# 10-Cooling_Sensors.net
KiCad netlist of a schematic drawn in Altium Designer
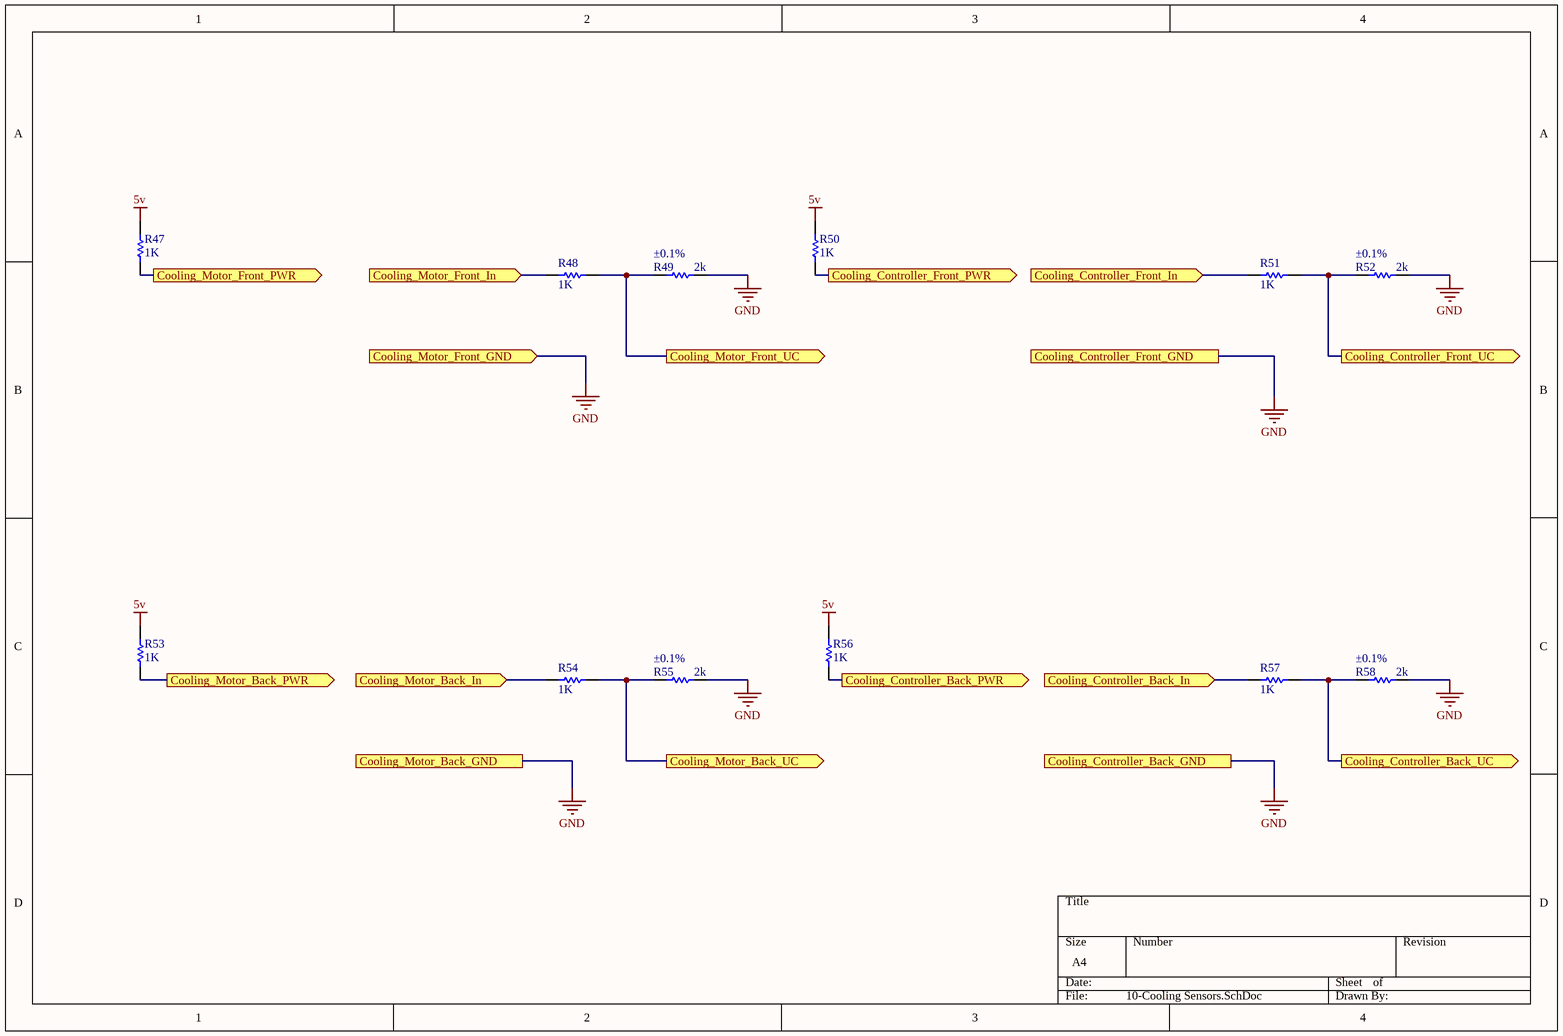
[diagram p0: 10-Cooling Sensors.SchDoc]

(export (version "E")
  (design (tool "Eeschema 10.0.6"))
  (components
    (comp (ref "R47")
      (value "1K")
      (footprint "1608[0603]")
      (description "Resistor")
      (fields (field (name "Comment") "Res1") (field (name "PUBLISHER") "Altium Limited"))
      (libsource (lib "Miscellaneous Devices") (part "Res1"))
    )
    (comp (ref "R48")
      (value "1K")
      (footprint "1608[0603]")
      (description "Resistor")
      (fields (field (name "Comment") "Res1") (field (name "PUBLISHER") "Altium Limited"))
      (libsource (lib "Miscellaneous Devices") (part "Res1"))
    )
    (comp (ref "R49")
      (value "2k")
      (footprint "1608[0603]")
      (description "Resistor")
      (fields
        (field (name "MANUFACTURER") "Yageo")
        (field (name "MANUFACTURER PART NUMBER") "AT0603BRD072KL")
        (field (name "TOLERANCE") "±0.1%")
      )
      (libsource (lib "Miscellaneous Devices") (part "Res1"))
    )
    (comp (ref "R50")
      (value "1K")
      (footprint "1608[0603]")
      (description "Resistor")
      (fields (field (name "Comment") "Res1") (field (name "PUBLISHER") "Altium Limited"))
      (libsource (lib "Miscellaneous Devices") (part "Res1"))
    )
    (comp (ref "R51")
      (value "1K")
      (footprint "1608[0603]")
      (description "Resistor")
      (fields (field (name "Comment") "Res1") (field (name "PUBLISHER") "Altium Limited"))
      (libsource (lib "Miscellaneous Devices") (part "Res1"))
    )
    (comp (ref "R52")
      (value "2k")
      (footprint "1608[0603]")
      (description "Resistor")
      (fields
        (field (name "MANUFACTURER") "Yageo")
        (field (name "MANUFACTURER PART NUMBER") "AT0603BRD072KL")
        (field (name "TOLERANCE") "±0.1%")
      )
      (libsource (lib "Miscellaneous Devices") (part "Res1"))
    )
    (comp (ref "R53")
      (value "1K")
      (footprint "1608[0603]")
      (description "Resistor")
      (fields (field (name "Comment") "Res1") (field (name "PUBLISHER") "Altium Limited"))
      (libsource (lib "Miscellaneous Devices") (part "Res1"))
    )
    (comp (ref "R54")
      (value "1K")
      (footprint "1608[0603]")
      (description "Resistor")
      (fields (field (name "Comment") "Res1") (field (name "PUBLISHER") "Altium Limited"))
      (libsource (lib "Miscellaneous Devices") (part "Res1"))
    )
    (comp (ref "R55")
      (value "2k")
      (footprint "1608[0603]")
      (description "Resistor")
      (fields
        (field (name "MANUFACTURER") "Yageo")
        (field (name "MANUFACTURER PART NUMBER") "AT0603BRD072KL")
        (field (name "TOLERANCE") "±0.1%")
      )
      (libsource (lib "Miscellaneous Devices") (part "Res1"))
    )
    (comp (ref "R56")
      (value "1K")
      (footprint "1608[0603]")
      (description "Resistor")
      (fields (field (name "Comment") "Res1") (field (name "PUBLISHER") "Altium Limited"))
      (libsource (lib "Miscellaneous Devices") (part "Res1"))
    )
    (comp (ref "R57")
      (value "1K")
      (footprint "1608[0603]")
      (description "Resistor")
      (fields (field (name "Comment") "Res1") (field (name "PUBLISHER") "Altium Limited"))
      (libsource (lib "Miscellaneous Devices") (part "Res1"))
    )
    (comp (ref "R58")
      (value "2k")
      (footprint "1608[0603]")
      (description "Resistor")
      (fields
        (field (name "MANUFACTURER") "Yageo")
        (field (name "MANUFACTURER PART NUMBER") "AT0603BRD072KL")
        (field (name "TOLERANCE") "±0.1%")
      )
      (libsource (lib "Miscellaneous Devices") (part "Res1"))
    )
  )
  (nets
    (net (code "1") (name "/Cooling_Controller_Back_In") (class "Default")
      (node (ref "R57") (pin "2") (pinfunction "2_2") (pintype "passive"))
    )
    (net (code "2") (name "/Cooling_Controller_Back_PWR") (class "Default")
      (node (ref "R56") (pin "1") (pinfunction "1_1") (pintype "passive"))
    )
    (net (code "3") (name "/Cooling_Controller_Back_UC") (class "Default")
      (node (ref "R57") (pin "1") (pinfunction "1_1") (pintype "passive"))
      (node (ref "R58") (pin "1") (pinfunction "1_1") (pintype "passive"))
    )
    (net (code "4") (name "/Cooling_Controller_Front_In") (class "Default")
      (node (ref "R51") (pin "2") (pinfunction "2_2") (pintype "passive"))
    )
    (net (code "5") (name "/Cooling_Controller_Front_PWR") (class "Default")
      (node (ref "R50") (pin "1") (pinfunction "1_1") (pintype "passive"))
    )
    (net (code "6") (name "/Cooling_Controller_Front_UC") (class "Default")
      (node (ref "R51") (pin "1") (pinfunction "1_1") (pintype "passive"))
      (node (ref "R52") (pin "1") (pinfunction "1_1") (pintype "passive"))
    )
    (net (code "7") (name "/Cooling_Motor_Back_In") (class "Default")
      (node (ref "R54") (pin "2") (pinfunction "2_2") (pintype "passive"))
    )
    (net (code "8") (name "/Cooling_Motor_Back_PWR") (class "Default")
      (node (ref "R53") (pin "1") (pinfunction "1_1") (pintype "passive"))
    )
    (net (code "9") (name "/Cooling_Motor_Back_UC") (class "Default")
      (node (ref "R54") (pin "1") (pinfunction "1_1") (pintype "passive"))
      (node (ref "R55") (pin "1") (pinfunction "1_1") (pintype "passive"))
    )
    (net (code "10") (name "/Cooling_Motor_Front_In") (class "Default")
      (node (ref "R48") (pin "2") (pinfunction "2_2") (pintype "passive"))
    )
    (net (code "11") (name "/Cooling_Motor_Front_PWR") (class "Default")
      (node (ref "R47") (pin "1") (pinfunction "1_1") (pintype "passive"))
    )
    (net (code "12") (name "/Cooling_Motor_Front_UC") (class "Default")
      (node (ref "R48") (pin "1") (pinfunction "1_1") (pintype "passive"))
      (node (ref "R49") (pin "1") (pinfunction "1_1") (pintype "passive"))
    )
    (net (code "13") (name "5v") (class "Default")
      (node (ref "R47") (pin "2") (pinfunction "2_2") (pintype "passive"))
      (node (ref "R50") (pin "2") (pinfunction "2_2") (pintype "passive"))
      (node (ref "R53") (pin "2") (pinfunction "2_2") (pintype "passive"))
      (node (ref "R56") (pin "2") (pinfunction "2_2") (pintype "passive"))
    )
    (net (code "14") (name "GND") (class "Default")
      (node (ref "R49") (pin "2") (pinfunction "2_2") (pintype "passive"))
      (node (ref "R52") (pin "2") (pinfunction "2_2") (pintype "passive"))
      (node (ref "R55") (pin "2") (pinfunction "2_2") (pintype "passive"))
      (node (ref "R58") (pin "2") (pinfunction "2_2") (pintype "passive"))
    )
  )
)
